# pump.net
KiCad netlist of a schematic drawn in Altium Designer
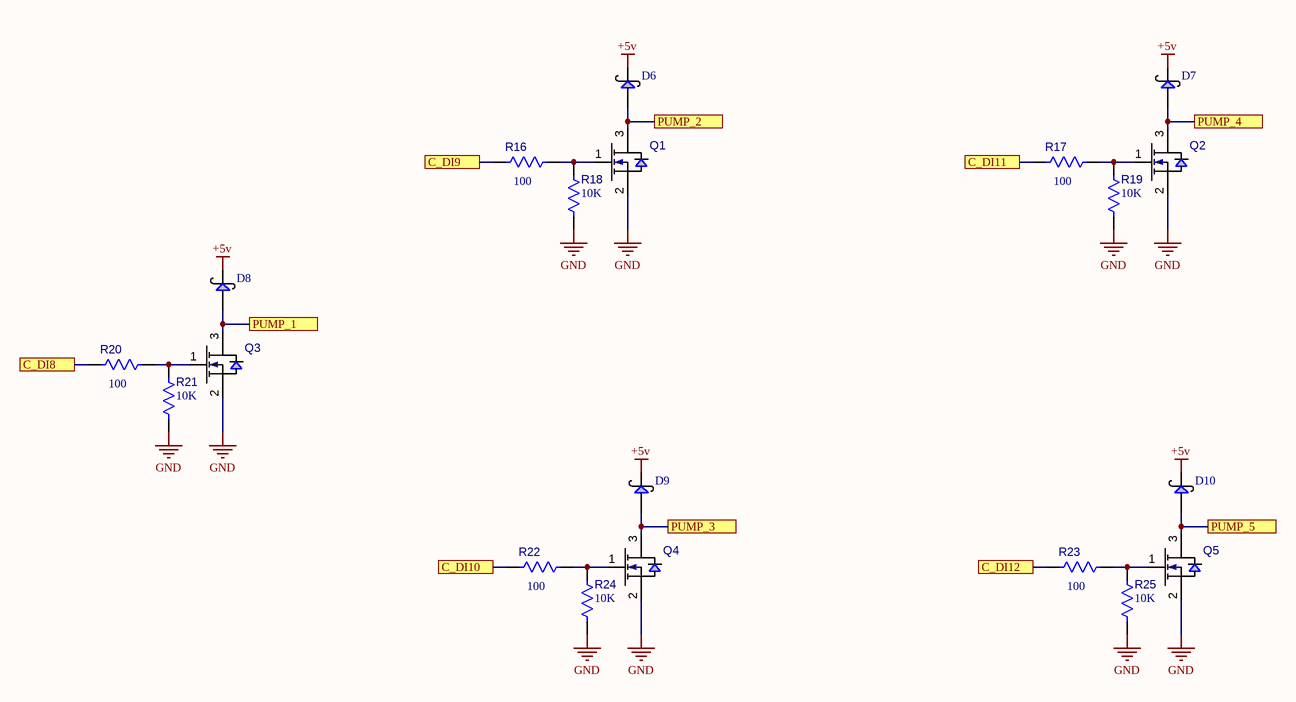
[diagram p0: pump.SchDoc]

(export (version "E")
  (design (tool "Eeschema 10.0.6"))
  (components
    (comp (ref "D6")
      (value "~")
      (footprint "SOD123")
      (description "SOD123")
      (libsource (lib "mylib") (part "MBRX160"))
    )
    (comp (ref "D7")
      (value "~")
      (footprint "SOD123")
      (description "SOD123")
      (libsource (lib "mylib") (part "MBRX160"))
    )
    (comp (ref "D8")
      (value "~")
      (footprint "SOD123")
      (description "SOD123")
      (libsource (lib "mylib") (part "MBRX160"))
    )
    (comp (ref "D9")
      (value "~")
      (footprint "SOD123")
      (description "SOD123")
      (libsource (lib "mylib") (part "MBRX160"))
    )
    (comp (ref "D10")
      (value "~")
      (footprint "SOD123")
      (description "SOD123")
      (libsource (lib "mylib") (part "MBRX160"))
    )
    (comp (ref "Q1")
      (value "BSS138")
      (footprint "SOT23_N_123")
      (description "N-Channel MOSFET")
      (fields (field (name "MANUFACTURER") "Fairchild"))
      (libsource (lib "mylib") (part "BSS138"))
    )
    (comp (ref "Q2")
      (value "BSS138")
      (footprint "SOT23_N_123")
      (description "N-Channel MOSFET")
      (fields (field (name "MANUFACTURER") "Fairchild"))
      (libsource (lib "mylib") (part "BSS138"))
    )
    (comp (ref "Q3")
      (value "BSS138")
      (footprint "SOT23_N_123")
      (description "N-Channel MOSFET")
      (fields (field (name "MANUFACTURER") "Fairchild"))
      (libsource (lib "mylib") (part "BSS138"))
    )
    (comp (ref "Q4")
      (value "BSS138")
      (footprint "SOT23_N_123")
      (description "N-Channel MOSFET")
      (fields (field (name "MANUFACTURER") "Fairchild"))
      (libsource (lib "mylib") (part "BSS138"))
    )
    (comp (ref "Q5")
      (value "BSS138")
      (footprint "SOT23_N_123")
      (description "N-Channel MOSFET")
      (fields (field (name "MANUFACTURER") "Fairchild"))
      (libsource (lib "mylib") (part "BSS138"))
    )
    (comp (ref "R16")
      (value "100")
      (footprint "0805")
      (description "Resistor")
      (fields (field (name "TOLERANCE") "1%"))
      (libsource (lib "mylib_franco") (part "Res"))
    )
    (comp (ref "R17")
      (value "100")
      (footprint "0805")
      (description "Resistor")
      (fields (field (name "TOLERANCE") "1%"))
      (libsource (lib "mylib_franco") (part "Res"))
    )
    (comp (ref "R18")
      (value "10K")
      (footprint "0805")
      (description "Resistor")
      (fields (field (name "TOLERANCE") "1%"))
      (libsource (lib "mylib") (part "Res"))
    )
    (comp (ref "R19")
      (value "10K")
      (footprint "0805")
      (description "Resistor")
      (fields (field (name "TOLERANCE") "1%"))
      (libsource (lib "mylib") (part "Res"))
    )
    (comp (ref "R20")
      (value "100")
      (footprint "0805")
      (description "Resistor")
      (fields (field (name "TOLERANCE") "1%"))
      (libsource (lib "mylib_franco") (part "Res"))
    )
    (comp (ref "R21")
      (value "10K")
      (footprint "0805")
      (description "Resistor")
      (fields (field (name "TOLERANCE") "1%"))
      (libsource (lib "mylib") (part "Res"))
    )
    (comp (ref "R22")
      (value "100")
      (footprint "0805")
      (description "Resistor")
      (fields (field (name "TOLERANCE") "1%"))
      (libsource (lib "mylib_franco") (part "Res"))
    )
    (comp (ref "R23")
      (value "100")
      (footprint "0805")
      (description "Resistor")
      (fields (field (name "TOLERANCE") "1%"))
      (libsource (lib "mylib_franco") (part "Res"))
    )
    (comp (ref "R24")
      (value "10K")
      (footprint "0805")
      (description "Resistor")
      (fields (field (name "TOLERANCE") "1%"))
      (libsource (lib "mylib") (part "Res"))
    )
    (comp (ref "R25")
      (value "10K")
      (footprint "0805")
      (description "Resistor")
      (fields (field (name "TOLERANCE") "1%"))
      (libsource (lib "mylib") (part "Res"))
    )
  )
  (nets
    (net (code "1") (name "+5v") (class "Default")
      (node (ref "D10") (pin "2") (pinfunction "2_2") (pintype "passive"))
      (node (ref "D6") (pin "2") (pinfunction "2_2") (pintype "passive"))
      (node (ref "D7") (pin "2") (pinfunction "2_2") (pintype "passive"))
      (node (ref "D8") (pin "2") (pinfunction "2_2") (pintype "passive"))
      (node (ref "D9") (pin "2") (pinfunction "2_2") (pintype "passive"))
    )
    (net (code "2") (name "/C_DI8") (class "Default")
      (node (ref "R20") (pin "1") (pinfunction "1_1") (pintype "passive"))
    )
    (net (code "3") (name "/C_DI9") (class "Default")
      (node (ref "R16") (pin "1") (pinfunction "1_1") (pintype "passive"))
    )
    (net (code "4") (name "/C_DI10") (class "Default")
      (node (ref "R22") (pin "1") (pinfunction "1_1") (pintype "passive"))
    )
    (net (code "5") (name "/C_DI11") (class "Default")
      (node (ref "R17") (pin "1") (pinfunction "1_1") (pintype "passive"))
    )
    (net (code "6") (name "/C_DI12") (class "Default")
      (node (ref "R23") (pin "1") (pinfunction "1_1") (pintype "passive"))
    )
    (net (code "7") (name "/PUMP_1") (class "Default")
      (node (ref "D8") (pin "1") (pinfunction "1_1") (pintype "passive"))
      (node (ref "Q3") (pin "3") (pinfunction "3_3") (pintype "passive"))
    )
    (net (code "8") (name "/PUMP_2") (class "Default")
      (node (ref "D6") (pin "1") (pinfunction "1_1") (pintype "passive"))
      (node (ref "Q1") (pin "3") (pinfunction "3_3") (pintype "passive"))
    )
    (net (code "9") (name "/PUMP_3") (class "Default")
      (node (ref "D9") (pin "1") (pinfunction "1_1") (pintype "passive"))
      (node (ref "Q4") (pin "3") (pinfunction "3_3") (pintype "passive"))
    )
    (net (code "10") (name "/PUMP_4") (class "Default")
      (node (ref "D7") (pin "1") (pinfunction "1_1") (pintype "passive"))
      (node (ref "Q2") (pin "3") (pinfunction "3_3") (pintype "passive"))
    )
    (net (code "11") (name "/PUMP_5") (class "Default")
      (node (ref "D10") (pin "1") (pinfunction "1_1") (pintype "passive"))
      (node (ref "Q5") (pin "3") (pinfunction "3_3") (pintype "passive"))
    )
    (net (code "12") (name "GND") (class "Default")
      (node (ref "Q1") (pin "2") (pinfunction "2_2") (pintype "passive"))
      (node (ref "Q2") (pin "2") (pinfunction "2_2") (pintype "passive"))
      (node (ref "Q3") (pin "2") (pinfunction "2_2") (pintype "passive"))
      (node (ref "Q4") (pin "2") (pinfunction "2_2") (pintype "passive"))
      (node (ref "Q5") (pin "2") (pinfunction "2_2") (pintype "passive"))
      (node (ref "R18") (pin "1") (pinfunction "1_1") (pintype "passive"))
      (node (ref "R19") (pin "1") (pinfunction "1_1") (pintype "passive"))
      (node (ref "R21") (pin "1") (pinfunction "1_1") (pintype "passive"))
      (node (ref "R24") (pin "1") (pinfunction "1_1") (pintype "passive"))
      (node (ref "R25") (pin "1") (pinfunction "1_1") (pintype "passive"))
    )
    (net (code "13") (name "Net-(Q1-Pad1)") (class "Default")
      (node (ref "Q1") (pin "1") (pinfunction "1_1") (pintype "passive"))
      (node (ref "R16") (pin "2") (pinfunction "2_2") (pintype "passive"))
      (node (ref "R18") (pin "2") (pinfunction "2_2") (pintype "passive"))
    )
    (net (code "14") (name "Net-(Q2-Pad1)") (class "Default")
      (node (ref "Q2") (pin "1") (pinfunction "1_1") (pintype "passive"))
      (node (ref "R17") (pin "2") (pinfunction "2_2") (pintype "passive"))
      (node (ref "R19") (pin "2") (pinfunction "2_2") (pintype "passive"))
    )
    (net (code "15") (name "Net-(Q3-Pad1)") (class "Default")
      (node (ref "Q3") (pin "1") (pinfunction "1_1") (pintype "passive"))
      (node (ref "R20") (pin "2") (pinfunction "2_2") (pintype "passive"))
      (node (ref "R21") (pin "2") (pinfunction "2_2") (pintype "passive"))
    )
    (net (code "16") (name "Net-(Q4-Pad1)") (class "Default")
      (node (ref "Q4") (pin "1") (pinfunction "1_1") (pintype "passive"))
      (node (ref "R22") (pin "2") (pinfunction "2_2") (pintype "passive"))
      (node (ref "R24") (pin "2") (pinfunction "2_2") (pintype "passive"))
    )
    (net (code "17") (name "Net-(Q5-Pad1)") (class "Default")
      (node (ref "Q5") (pin "1") (pinfunction "1_1") (pintype "passive"))
      (node (ref "R23") (pin "2") (pinfunction "2_2") (pintype "passive"))
      (node (ref "R25") (pin "2") (pinfunction "2_2") (pintype "passive"))
    )
  )
)
